# SCH.net
KiCad netlist of a schematic drawn in EasyEDA
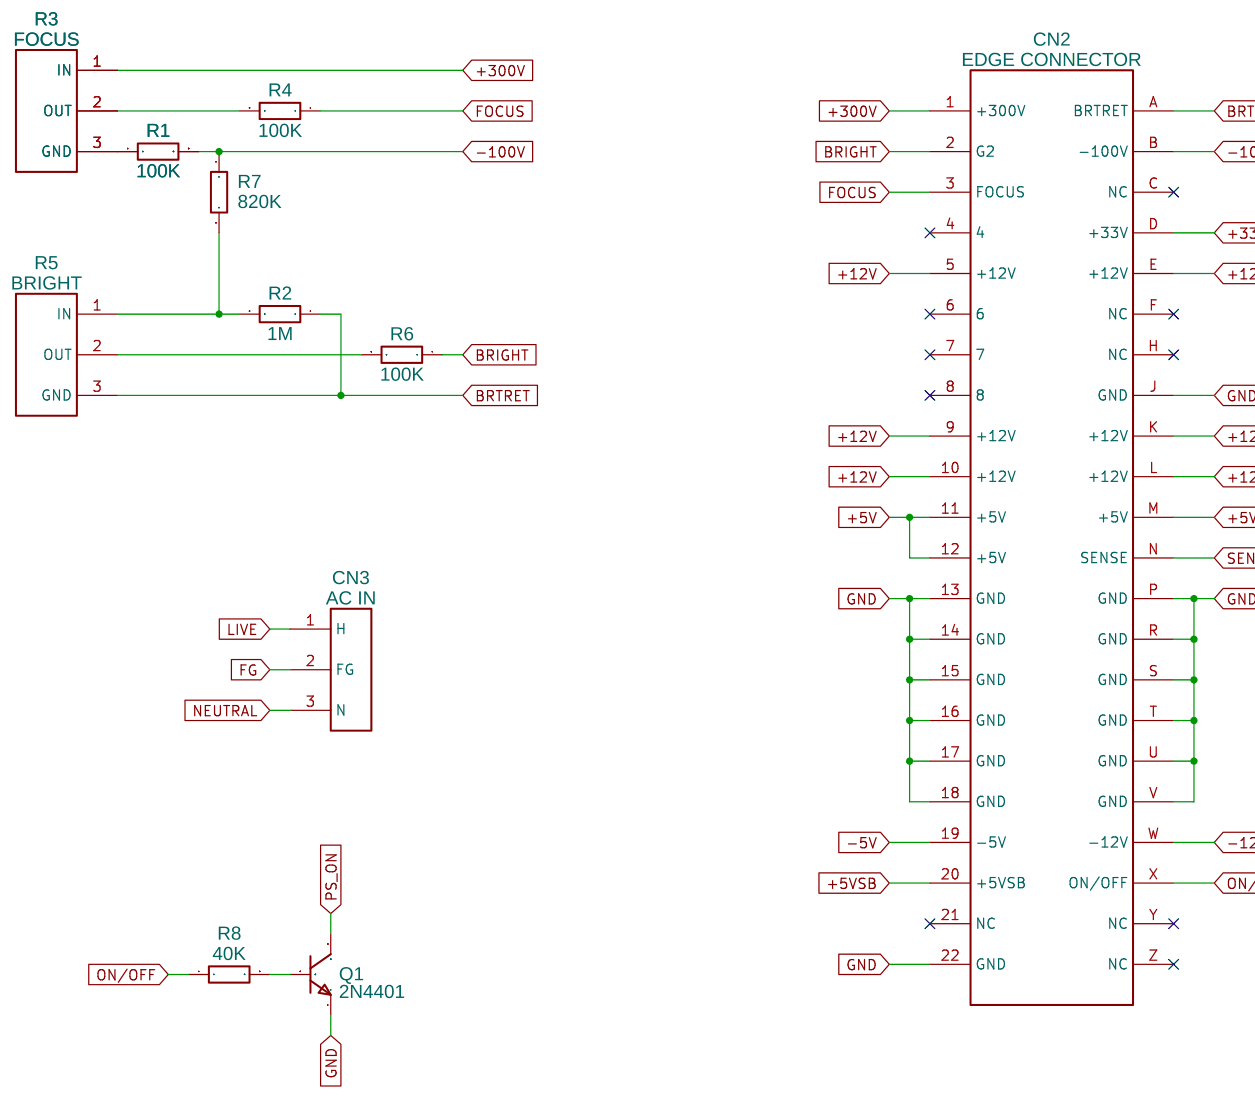
[diagram p0: schematic sheet]

(export (version "E")
  (design (tool "Eeschema 10.0.6"))
  (components
    (comp (ref "CN2") (value "EDGE CONNECTOR") (libsource (lib "") (part "LISA_PSU_EDGE_CONNECTOR")))
    (comp (ref "CN3") (value "AC IN") (libsource (lib "") (part "LISA_PSU_AC_IN")))
    (comp (ref "Q1")
      (value "2N4401")
      (fields (field (name "BOM_Supplier Part") "C118540"))
      (libsource (lib "") (part "2N4401-C118540"))
    )
    (comp (ref "R1") (value "100K") (libsource (lib "") (part "LISA_CPU_RESISTOR_1")))
    (comp (ref "R2") (value "1M") (libsource (lib "") (part "LISA_CPU_RESISTOR")))
    (comp (ref "R3") (value "FOCUS") (libsource (lib "") (part "LISA_CRT_POT")))
    (comp (ref "R4") (value "100K") (libsource (lib "") (part "LISA_CPU_RESISTOR")))
    (comp (ref "R5") (value "BRIGHT") (libsource (lib "") (part "LISA_CRT_POT")))
    (comp (ref "R6") (value "100K") (libsource (lib "") (part "LISA_CPU_RESISTOR")))
    (comp (ref "R7") (value "820K") (libsource (lib "") (part "LISA_CPU_RESISTOR_2")))
    (comp (ref "R8") (value "40K") (libsource (lib "") (part "LISA_CPU_RESISTOR_1")))
  )
  (nets
    (net (code "1") (name "+5V") (class "Default")
      (node (ref "CN2") (pin "11") (pinfunction "+5V_11") (pintype "unspecified"))
      (node (ref "CN2") (pin "12") (pinfunction "+5V_12") (pintype "unspecified"))
      (node (ref "CN2") (pin "M") (pinfunction "+5V_M") (pintype "unspecified"))
    )
    (net (code "2") (name "+5VSB") (class "Default")
      (node (ref "CN2") (pin "20") (pinfunction "+5VSB_20") (pintype "unspecified"))
    )
    (net (code "3") (name "+12V") (class "Default")
      (node (ref "CN2") (pin "10") (pinfunction "+12V_10") (pintype "unspecified"))
      (node (ref "CN2") (pin "5") (pinfunction "+12V_5") (pintype "unspecified"))
      (node (ref "CN2") (pin "9") (pinfunction "+12V_9") (pintype "unspecified"))
      (node (ref "CN2") (pin "E") (pinfunction "+12V_E") (pintype "unspecified"))
      (node (ref "CN2") (pin "K") (pinfunction "+12V_K") (pintype "unspecified"))
      (node (ref "CN2") (pin "L") (pinfunction "+12V_L") (pintype "unspecified"))
    )
    (net (code "4") (name "+33V") (class "Default")
      (node (ref "CN2") (pin "D") (pinfunction "+33V_D") (pintype "unspecified"))
    )
    (net (code "5") (name "+300V") (class "Default")
      (node (ref "CN2") (pin "1") (pinfunction "+300V_1") (pintype "unspecified"))
      (node (ref "R3") (pin "1") (pinfunction "IN_1") (pintype "unspecified"))
    )
    (net (code "6") (name "-5V") (class "Default")
      (node (ref "CN2") (pin "19") (pinfunction "-5V_19") (pintype "unspecified"))
    )
    (net (code "7") (name "-12V") (class "Default")
      (node (ref "CN2") (pin "W") (pinfunction "-12V_W") (pintype "unspecified"))
    )
    (net (code "8") (name "-100V") (class "Default")
      (node (ref "CN2") (pin "B") (pinfunction "-100V_B") (pintype "unspecified"))
      (node (ref "R1") (pin "2") (pinfunction "2_2") (pintype "unspecified"))
      (node (ref "R7") (pin "1") (pinfunction "1_1") (pintype "unspecified"))
    )
    (net (code "9") (name "BRIGHT") (class "Default")
      (node (ref "CN2") (pin "2") (pinfunction "G2_2") (pintype "unspecified"))
      (node (ref "R6") (pin "1") (pinfunction "1_1") (pintype "unspecified"))
    )
    (net (code "10") (name "BRTRET") (class "Default")
      (node (ref "CN2") (pin "A") (pinfunction "BRTRET_A") (pintype "unspecified"))
      (node (ref "R2") (pin "1") (pinfunction "1_1") (pintype "unspecified"))
      (node (ref "R5") (pin "3") (pinfunction "GND_3") (pintype "unspecified"))
    )
    (net (code "11") (name "FG") (class "Default")
      (node (ref "CN3") (pin "2") (pinfunction "FG_2") (pintype "unspecified"))
    )
    (net (code "12") (name "FOCUS") (class "Default")
      (node (ref "CN2") (pin "3") (pinfunction "FOCUS_3") (pintype "unspecified"))
      (node (ref "R4") (pin "1") (pinfunction "1_1") (pintype "unspecified"))
    )
    (net (code "13") (name "GND") (class "Default")
      (node (ref "CN2") (pin "13") (pinfunction "GND_13") (pintype "unspecified"))
      (node (ref "CN2") (pin "14") (pinfunction "GND_14") (pintype "unspecified"))
      (node (ref "CN2") (pin "15") (pinfunction "GND_15") (pintype "unspecified"))
      (node (ref "CN2") (pin "16") (pinfunction "GND_16") (pintype "unspecified"))
      (node (ref "CN2") (pin "17") (pinfunction "GND_17") (pintype "unspecified"))
      (node (ref "CN2") (pin "18") (pinfunction "GND_18") (pintype "unspecified"))
      (node (ref "CN2") (pin "22") (pinfunction "GND_22") (pintype "unspecified"))
      (node (ref "CN2") (pin "J") (pinfunction "GND_J") (pintype "unspecified"))
      (node (ref "CN2") (pin "P") (pinfunction "GND_P") (pintype "unspecified"))
      (node (ref "CN2") (pin "R") (pinfunction "GND_R") (pintype "unspecified"))
      (node (ref "CN2") (pin "S") (pinfunction "GND_S") (pintype "unspecified"))
      (node (ref "CN2") (pin "T") (pinfunction "GND_T") (pintype "unspecified"))
      (node (ref "CN2") (pin "U") (pinfunction "GND_U") (pintype "unspecified"))
      (node (ref "CN2") (pin "V") (pinfunction "GND_V") (pintype "unspecified"))
      (node (ref "Q1") (pin "1") (pinfunction "E_1") (pintype "unspecified"))
    )
    (net (code "14") (name "LIVE") (class "Default")
      (node (ref "CN3") (pin "1") (pinfunction "H_1") (pintype "unspecified"))
    )
    (net (code "15") (name "NEUTRAL") (class "Default")
      (node (ref "CN3") (pin "3") (pinfunction "N_3") (pintype "unspecified"))
    )
    (net (code "16") (name "Net-(Q1-B)") (class "Default")
      (node (ref "Q1") (pin "2") (pinfunction "B_2") (pintype "unspecified"))
      (node (ref "R8") (pin "2") (pinfunction "2_2") (pintype "unspecified"))
    )
    (net (code "17") (name "Net-(R3-GND)") (class "Default")
      (node (ref "R1") (pin "1") (pinfunction "1_1") (pintype "unspecified"))
      (node (ref "R3") (pin "3") (pinfunction "GND_3") (pintype "unspecified"))
    )
    (net (code "18") (name "Net-(R3-OUT)") (class "Default")
      (node (ref "R3") (pin "2") (pinfunction "OUT_2") (pintype "unspecified"))
      (node (ref "R4") (pin "2") (pinfunction "2_2") (pintype "unspecified"))
    )
    (net (code "19") (name "Net-(R5-IN)") (class "Default")
      (node (ref "R2") (pin "2") (pinfunction "2_2") (pintype "unspecified"))
      (node (ref "R5") (pin "1") (pinfunction "IN_1") (pintype "unspecified"))
      (node (ref "R7") (pin "2") (pinfunction "2_2") (pintype "unspecified"))
    )
    (net (code "20") (name "Net-(R5-OUT)") (class "Default")
      (node (ref "R5") (pin "2") (pinfunction "OUT_2") (pintype "unspecified"))
      (node (ref "R6") (pin "2") (pinfunction "2_2") (pintype "unspecified"))
    )
    (net (code "21") (name "ON{slash}OFF") (class "Default")
      (node (ref "CN2") (pin "X") (pinfunction "ON/OFF_X") (pintype "unspecified"))
      (node (ref "R8") (pin "1") (pinfunction "1_1") (pintype "unspecified"))
    )
    (net (code "22") (name "PS_ON") (class "Default")
      (node (ref "Q1") (pin "3") (pinfunction "C_3") (pintype "unspecified"))
    )
    (net (code "23") (name "SENSE") (class "Default")
      (node (ref "CN2") (pin "N") (pinfunction "SENSE_N") (pintype "unspecified"))
    )
    (net (code "24") (name "unconnected-(CN2-NC-Pad21)") (class "Default")
      (node (ref "CN2") (pin "21") (pinfunction "NC_21") (pintype "unspecified+no_connect"))
    )
    (net (code "25") (name "unconnected-(CN2-NC-PadC)") (class "Default")
      (node (ref "CN2") (pin "C") (pinfunction "NC_C") (pintype "unspecified+no_connect"))
    )
    (net (code "26") (name "unconnected-(CN2-NC-PadF)") (class "Default")
      (node (ref "CN2") (pin "F") (pinfunction "NC_F") (pintype "unspecified+no_connect"))
    )
    (net (code "27") (name "unconnected-(CN2-NC-PadH)") (class "Default")
      (node (ref "CN2") (pin "H") (pinfunction "NC_H") (pintype "unspecified+no_connect"))
    )
    (net (code "28") (name "unconnected-(CN2-NC-PadY)") (class "Default")
      (node (ref "CN2") (pin "Y") (pinfunction "NC_Y") (pintype "unspecified+no_connect"))
    )
    (net (code "29") (name "unconnected-(CN2-NC-PadZ)") (class "Default")
      (node (ref "CN2") (pin "Z") (pinfunction "NC_Z") (pintype "unspecified+no_connect"))
    )
    (net (code "30") (name "unconnected-(CN2-Pad4)") (class "Default")
      (node (ref "CN2") (pin "4") (pinfunction "4_4") (pintype "unspecified+no_connect"))
    )
    (net (code "31") (name "unconnected-(CN2-Pad6)") (class "Default")
      (node (ref "CN2") (pin "6") (pinfunction "6_6") (pintype "unspecified+no_connect"))
    )
    (net (code "32") (name "unconnected-(CN2-Pad7)") (class "Default")
      (node (ref "CN2") (pin "7") (pinfunction "7_7") (pintype "unspecified+no_connect"))
    )
    (net (code "33") (name "unconnected-(CN2-Pad8)") (class "Default")
      (node (ref "CN2") (pin "8") (pinfunction "8_8") (pintype "unspecified+no_connect"))
    )
  )
)
